# Sensor-Board.net
KiCad netlist of a schematic drawn in Altium Designer
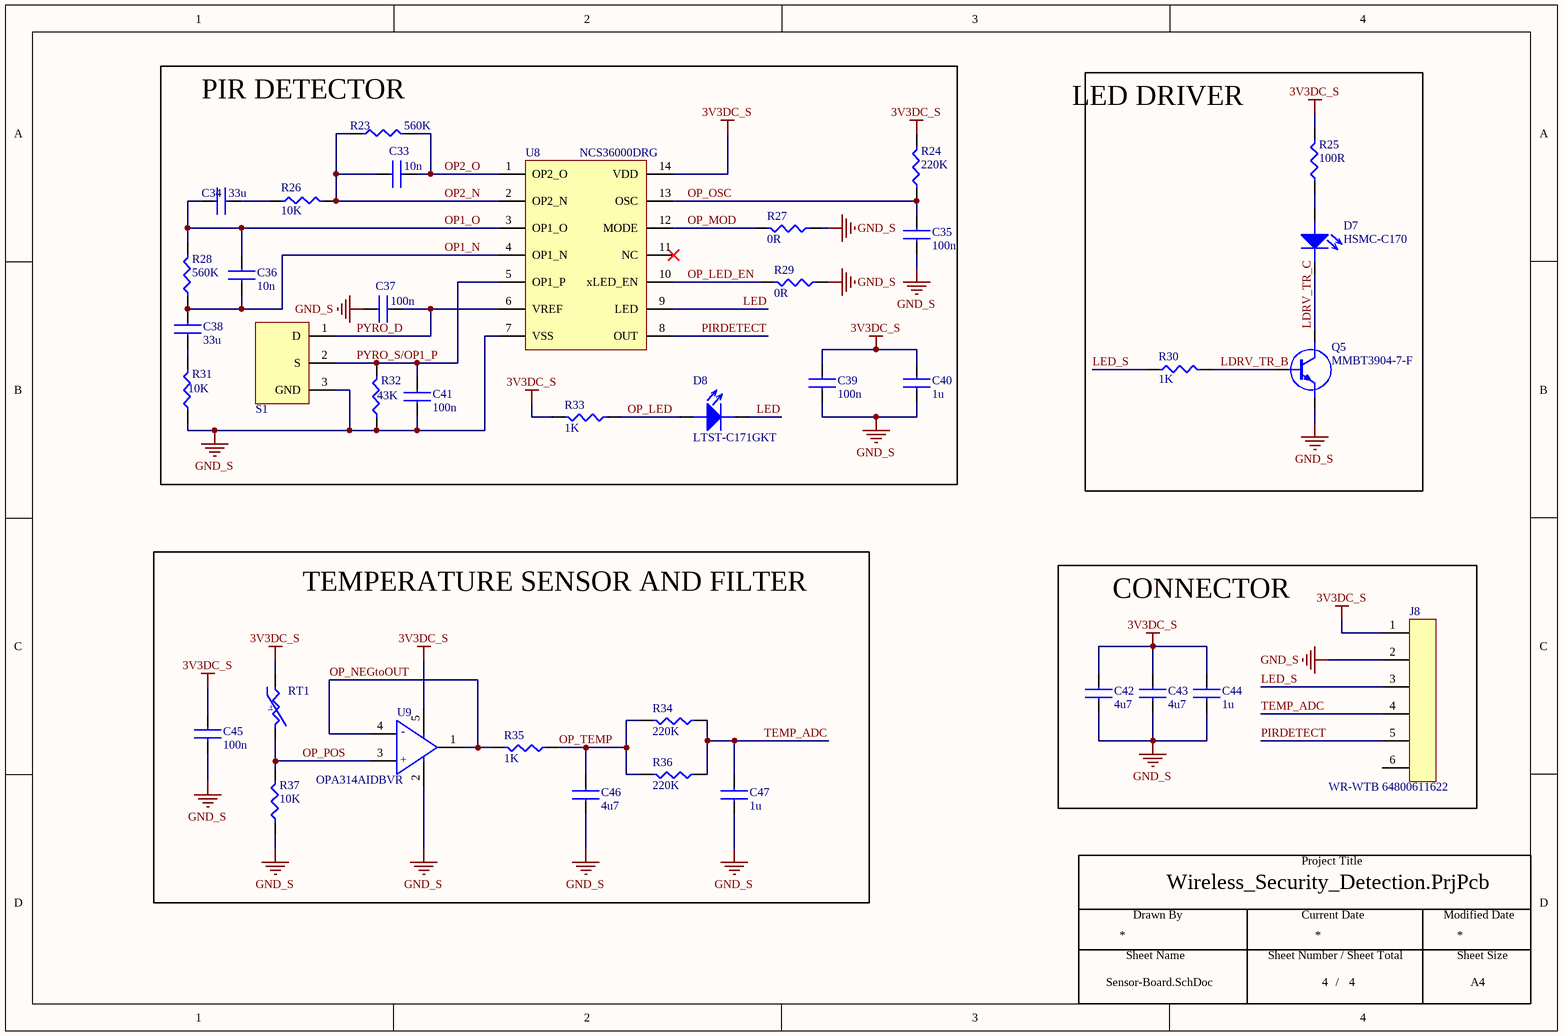
[diagram p0: Sensor-Board.SchDoc]

(export (version "E")
  (design (tool "Eeschema 10.0.6"))
  (components
    (comp (ref "C33")
      (value "10n")
      (footprint "CAPACITOR 0603")
      (description "0603 16V X7R 10nF 10% multilayer ceramic capacitor")
      (fields
        (field (name "MANUFACTURER") "Walsin Technologies")
        (field (name "MANUFACTURER PART NUMBER") "0603B103K160CT")
        (field (name "DESIGNED BY") "UK")
      )
      (libsource (lib "UKLIB") (part "CAP CER 10nF 0603"))
    )
    (comp (ref "C34")
      (value "33u")
      (footprint "CAPACITOR 1206")
      (description "Multilayer Ceramic Capacitor, 33 uF, 25 V, ± 20%, X5R, 1206 [3216 Metric]")
      (fields
        (field (name "MANUFACTURER") "TDK")
        (field (name "MANUFACTURER PART NUMBER") "C3216X5R1E336M160AC")
        (field (name "DESIGNED BY") "UK")
      )
      (libsource (lib "UKLIB") (part "CAP CER 33uF 1206"))
    )
    (comp (ref "C35")
      (value "100n")
      (footprint "Capacitor 0603")
      (description "Multilayer Ceramic Capacitor, 0.1 uF, 50 V, ± 10%, X7R, 0603 [1608 Metric]")
      (fields
        (field (name "MANUFACTURER") "KEMET")
        (field (name "MANUFACTURER PART NUMBER") "C0603C104K5RACTU")
        (field (name "DESIGNED BY") "UK")
      )
      (libsource (lib "UKLIB") (part "CAP CER 100nF 0603"))
    )
    (comp (ref "C36")
      (value "10n")
      (footprint "CAPACITOR 0603")
      (description "0603 16V X7R 10nF 10% multilayer ceramic capacitor")
      (fields
        (field (name "MANUFACTURER") "Walsin Technologies")
        (field (name "MANUFACTURER PART NUMBER") "0603B103K160CT")
        (field (name "DESIGNED BY") "UK")
      )
      (libsource (lib "UKLIB") (part "CAP CER 10nF 0603"))
    )
    (comp (ref "C37")
      (value "100n")
      (footprint "Capacitor 0603")
      (description "Multilayer Ceramic Capacitor, 0.1 uF, 50 V, ± 10%, X7R, 0603 [1608 Metric]")
      (fields
        (field (name "MANUFACTURER") "KEMET")
        (field (name "MANUFACTURER PART NUMBER") "C0603C104K5RACTU")
        (field (name "DESIGNED BY") "UK")
      )
      (libsource (lib "UKLIB") (part "CAP CER 100nF 0603"))
    )
    (comp (ref "C38")
      (value "33u")
      (footprint "CAPACITOR 1206")
      (description "Multilayer Ceramic Capacitor, 33 uF, 25 V, ± 20%, X5R, 1206 [3216 Metric]")
      (fields
        (field (name "MANUFACTURER") "TDK")
        (field (name "MANUFACTURER PART NUMBER") "C3216X5R1E336M160AC")
        (field (name "DESIGNED BY") "UK")
      )
      (libsource (lib "UKLIB") (part "CAP CER 33uF 1206"))
    )
    (comp (ref "C39")
      (value "100n")
      (footprint "Capacitor 0603")
      (description "Multilayer Ceramic Capacitor, 0.1 uF, 50 V, ± 10%, X7R, 0603 [1608 Metric]")
      (fields
        (field (name "MANUFACTURER") "KEMET")
        (field (name "MANUFACTURER PART NUMBER") "C0603C104K5RACTU")
        (field (name "DESIGNED BY") "UK")
      )
      (libsource (lib "UKLIB") (part "CAP CER 100nF 0603"))
    )
    (comp (ref "C40")
      (value "1u")
      (footprint "CAPACITOR 0805 - duplicate")
      (description "Multilayer Ceramic Capacitor, 1 uF, 50 V, ± 10%, X7R, 0805 [2012 Metric]")
      (fields
        (field (name "MANUFACTURER") "Samsung")
        (field (name "MANUFACTURER PART NUMBER") "CL21B105KBFNNNE")
        (field (name "DESIGNED BY") "UK")
      )
      (libsource (lib "UKLIB") (part "CAP CER 1uF 0805"))
    )
    (comp (ref "C41")
      (value "100n")
      (footprint "Capacitor 0603")
      (description "Multilayer Ceramic Capacitor, 0.1 uF, 50 V, ± 10%, X7R, 0603 [1608 Metric]")
      (fields
        (field (name "MANUFACTURER") "KEMET")
        (field (name "MANUFACTURER PART NUMBER") "C0603C104K5RACTU")
        (field (name "DESIGNED BY") "UK")
      )
      (libsource (lib "UKLIB") (part "CAP CER 100nF 0603"))
    )
    (comp (ref "C42")
      (value "4u7")
      (footprint "CAPACITOR 0805 - duplicate")
      (description "Multilayer Ceramic Capacitor, 4.7 uF, 25 V, ± 10%, X5R, 0805 [2012 Metric]")
      (fields
        (field (name "MANUFACTURER") "Samsung")
        (field (name "MANUFACTURER PART NUMBER") "CL21A475KAQNNNE")
        (field (name "DESIGNED BY") "UK")
      )
      (libsource (lib "UKLIB") (part "CAP CER 4.7uF 0805"))
    )
    (comp (ref "C43")
      (value "4u7")
      (footprint "CAPACITOR 0805 - duplicate")
      (description "Multilayer Ceramic Capacitor, 4.7 uF, 25 V, ± 10%, X5R, 0805 [2012 Metric]")
      (fields
        (field (name "MANUFACTURER") "Samsung")
        (field (name "MANUFACTURER PART NUMBER") "CL21A475KAQNNNE")
        (field (name "DESIGNED BY") "UK")
      )
      (libsource (lib "UKLIB") (part "CAP CER 4.7uF 0805"))
    )
    (comp (ref "C44")
      (value "1u")
      (footprint "CAPACITOR 0805 - duplicate")
      (description "Multilayer Ceramic Capacitor, 1 uF, 50 V, ± 10%, X7R, 0805 [2012 Metric]")
      (fields
        (field (name "MANUFACTURER") "Samsung")
        (field (name "MANUFACTURER PART NUMBER") "CL21B105KBFNNNE")
        (field (name "DESIGNED BY") "UK")
      )
      (libsource (lib "UKLIB") (part "CAP CER 1uF 0805"))
    )
    (comp (ref "C45")
      (value "100n")
      (footprint "Capacitor 0603")
      (description "Multilayer Ceramic Capacitor, 0.1 uF, 50 V, ± 10%, X7R, 0603 [1608 Metric]")
      (fields
        (field (name "MANUFACTURER") "KEMET")
        (field (name "MANUFACTURER PART NUMBER") "C0603C104K5RACTU")
        (field (name "DESIGNED BY") "UK")
      )
      (libsource (lib "UKLIB") (part "CAP CER 100nF 0603"))
    )
    (comp (ref "C46")
      (value "4u7")
      (footprint "CAPACITOR 0805 - duplicate")
      (description "Multilayer Ceramic Capacitor, 4.7 uF, 25 V, ± 10%, X5R, 0805 [2012 Metric]")
      (fields
        (field (name "MANUFACTURER") "Samsung")
        (field (name "MANUFACTURER PART NUMBER") "CL21A475KAQNNNE")
        (field (name "DESIGNED BY") "UK")
      )
      (libsource (lib "UKLIB") (part "CAP CER 4.7uF 0805"))
    )
    (comp (ref "C47")
      (value "1u")
      (footprint "CAPACITOR 0805 - duplicate")
      (description "Multilayer Ceramic Capacitor, 1 uF, 50 V, ± 10%, X7R, 0805 [2012 Metric]")
      (fields
        (field (name "MANUFACTURER") "Samsung")
        (field (name "MANUFACTURER PART NUMBER") "CL21B105KBFNNNE")
        (field (name "DESIGNED BY") "UK")
      )
      (libsource (lib "UKLIB") (part "CAP CER 1uF 0805"))
    )
    (comp (ref "D7")
      (value "HSMC-C170")
      (footprint "LED RED 0805")
      (description "Single Color LED, Red, Untinted Diffused, 1.4mm")
      (fields (field (name "MANUFACTURER") "Broadcom Avago") (field (name "DESIGNED BY") "UK"))
      (libsource (lib "UKLIB") (part "LED RED 0805"))
    )
    (comp (ref "D8")
      (value "LTST-C171GKT")
      (footprint "LED GREEN 0805")
      (description "LED Low-Power Uni-Color Green 565nm 2.1V 2-Pin Chip LED T/R")
      (fields (field (name "MANUFACTURER") "Vishay Lite-On") (field (name "DESIGNED BY") "UK"))
      (libsource (lib "UKLIB") (part "LED GREEN 0805"))
    )
    (comp (ref "J8")
      (value "WR-WTB 64800611622")
      (footprint "6P SMD TERMINAL 1.50 MALE")
      (description "WR-WTB Wire-to-Board Connectors 1.50 mm")
      (fields
        (field (name "MANUFACTURER") "Wurth Electronics")
        (field (name "MANUFACTURER PART NUMBER") "64800611622")
        (field (name "DESIGNED BY") "UK")
      )
      (libsource (lib "UKLIB") (part "6P SMD TERMINAL 1.50 MALE"))
    )
    (comp (ref "Q5")
      (value "MMBT3904-7-F")
      (footprint "SOT-23F")
      (description "Transistor General Purpose BJT NPN 40 Volt 0.2A Automotive 3-Pin SOT-23")
      (fields (field (name "MANUFACTURER") "Diodes Zetex") (field (name "DESIGNED BY") "UK"))
      (libsource (lib "UKLIB") (part "MMBT3904-7-F"))
    )
    (comp (ref "R23")
      (value "560K")
      (footprint "Resistor 0603")
      (description "SMD Chip Resistor, 560 kOhm, ± 5%, 100 mW, 0603 [1608 Metric], Thick Film, General Purpose")
      (fields
        (field (name "MANUFACTURER") "Yageo")
        (field (name "MANUFACTURER PART NUMBER") "RC0603JR-07560KL")
        (field (name "DESIGNED BY") "UK")
      )
      (libsource (lib "UKLIB") (part "RES 560K 0603"))
    )
    (comp (ref "R24")
      (value "220K")
      (footprint "Resistor 0603")
      (description "SMD Chip Resistor, 220 kOhm, ± 5%, 100 mW, 0603 [1608 Metric], Thick Film, General Purpose")
      (fields
        (field (name "MANUFACTURER") "Yageo")
        (field (name "MANUFACTURER PART NUMBER") "RC0603JR-07220KL")
        (field (name "DESIGNED BY") "UK")
      )
      (libsource (lib "UKLIB") (part "RES 220K 0603"))
    )
    (comp (ref "R25")
      (value "100R")
      (footprint "Resistor 0603")
      (description "SMD Chip Resistor, 100 Ohm, ± 5%, 100 mW, 0603 [1608 Metric], Thick Film, General Purpose")
      (fields
        (field (name "MANUFACTURER") "Yageo")
        (field (name "MANUFACTURER PART NUMBER") "RC0603JR-07100RL")
        (field (name "DESIGNED BY") "UK")
      )
      (libsource (lib "UKLIB") (part "RES 100R 0603"))
    )
    (comp (ref "R26")
      (value "10K")
      (footprint "Resistor 0603")
      (description "SMD Chip Resistor, 10 kOhm, ± 1%, 100 mW, 0603 [1608 Metric], Thick Film, General Purpose")
      (fields
        (field (name "MANUFACTURER") "Yageo")
        (field (name "MANUFACTURER PART NUMBER") "RC0603FR-0710KL")
        (field (name "DESIGNED BY") "UK")
      )
      (libsource (lib "UKLIB") (part "RES 10K 0603"))
    )
    (comp (ref "R27")
      (value "0R")
      (footprint "Resistor 0603")
      (description "GENERAL PURPOSE CHIP RESISTOR Metal Glaze/thick Film, 0.1W, 0ohm, Surface Mount, 0603")
      (fields
        (field (name "MANUFACTURER") "Yageo")
        (field (name "MANUFACTURER PART NUMBER") "RC0603JR-070RL")
        (field (name "DESIGNED BY") "UK")
      )
      (libsource (lib "UKLIB") (part "RES 0R 0603"))
    )
    (comp (ref "R28")
      (value "560K")
      (footprint "Resistor 0603")
      (description "SMD Chip Resistor, 560 kOhm, ± 5%, 100 mW, 0603 [1608 Metric], Thick Film, General Purpose")
      (fields
        (field (name "MANUFACTURER") "Yageo")
        (field (name "MANUFACTURER PART NUMBER") "RC0603JR-07560KL")
        (field (name "DESIGNED BY") "UK")
      )
      (libsource (lib "UKLIB") (part "RES 560K 0603"))
    )
    (comp (ref "R29")
      (value "0R")
      (footprint "Resistor 0603")
      (description "GENERAL PURPOSE CHIP RESISTOR Metal Glaze/thick Film, 0.1W, 0ohm, Surface Mount, 0603")
      (fields
        (field (name "MANUFACTURER") "Yageo")
        (field (name "MANUFACTURER PART NUMBER") "RC0603JR-070RL")
        (field (name "DESIGNED BY") "UK")
      )
      (libsource (lib "UKLIB") (part "RES 0R 0603"))
    )
    (comp (ref "R30")
      (value "1K")
      (footprint "Resistor 0603")
      (description "SMD Chip Resistor, 1 kOhm, ± 1%, 100 mW, 0603 [1608 Metric], Thick Film, General Purpose")
      (fields
        (field (name "MANUFACTURER") "Yageo")
        (field (name "MANUFACTURER PART NUMBER") "RC0603FR-071KL")
        (field (name "DESIGNED BY") "UK")
      )
      (libsource (lib "UKLIB") (part "RES 1K 0603"))
    )
    (comp (ref "R31")
      (value "10K")
      (footprint "Resistor 0603")
      (description "SMD Chip Resistor, 10 kOhm, ± 1%, 100 mW, 0603 [1608 Metric], Thick Film, General Purpose")
      (fields
        (field (name "MANUFACTURER") "Yageo")
        (field (name "MANUFACTURER PART NUMBER") "RC0603FR-0710KL")
        (field (name "DESIGNED BY") "UK")
      )
      (libsource (lib "UKLIB") (part "RES 10K 0603"))
    )
    (comp (ref "R32")
      (value "43K")
      (footprint "Resistor 0603")
      (description "Res Thick Film 0603 43K Ohm 5% 0.1W(1/10W) ±100ppm/°C Pad SMD T/R")
      (fields
        (field (name "MANUFACTURER") "Yageo")
        (field (name "MANUFACTURER PART NUMBER") "RC0603JR-0743KL")
        (field (name "DESIGNED BY") "UK")
      )
      (libsource (lib "UKLIB") (part "RES 43K 0603"))
    )
    (comp (ref "R33")
      (value "1K")
      (footprint "Resistor 0603")
      (description "SMD Chip Resistor, 1 kOhm, ± 1%, 100 mW, 0603 [1608 Metric], Thick Film, General Purpose")
      (fields
        (field (name "MANUFACTURER") "Yageo")
        (field (name "MANUFACTURER PART NUMBER") "RC0603FR-071KL")
        (field (name "DESIGNED BY") "UK")
      )
      (libsource (lib "UKLIB") (part "RES 1K 0603"))
    )
    (comp (ref "R34")
      (value "220K")
      (footprint "Resistor 0603")
      (description "SMD Chip Resistor, 220 kOhm, ± 5%, 100 mW, 0603 [1608 Metric], Thick Film, General Purpose")
      (fields
        (field (name "MANUFACTURER") "Yageo")
        (field (name "MANUFACTURER PART NUMBER") "RC0603JR-07220KL")
        (field (name "DESIGNED BY") "UK")
      )
      (libsource (lib "UKLIB") (part "RES 220K 0603"))
    )
    (comp (ref "R35")
      (value "1K")
      (footprint "Resistor 0603")
      (description "SMD Chip Resistor, 1 kOhm, ± 1%, 100 mW, 0603 [1608 Metric], Thick Film, General Purpose")
      (fields
        (field (name "MANUFACTURER") "Yageo")
        (field (name "MANUFACTURER PART NUMBER") "RC0603FR-071KL")
        (field (name "DESIGNED BY") "UK")
      )
      (libsource (lib "UKLIB") (part "RES 1K 0603"))
    )
    (comp (ref "R36")
      (value "220K")
      (footprint "Resistor 0603")
      (description "SMD Chip Resistor, 220 kOhm, ± 5%, 100 mW, 0603 [1608 Metric], Thick Film, General Purpose")
      (fields
        (field (name "MANUFACTURER") "Yageo")
        (field (name "MANUFACTURER PART NUMBER") "RC0603JR-07220KL")
        (field (name "DESIGNED BY") "UK")
      )
      (libsource (lib "UKLIB") (part "RES 220K 0603"))
    )
    (comp (ref "R37")
      (value "10K")
      (footprint "Resistor 0603")
      (description "SMD Chip Resistor, 10 kOhm, ± 1%, 100 mW, 0603 [1608 Metric], Thick Film, General Purpose")
      (fields
        (field (name "MANUFACTURER") "Yageo")
        (field (name "MANUFACTURER PART NUMBER") "RC0603FR-0710KL")
        (field (name "DESIGNED BY") "UK")
      )
      (libsource (lib "UKLIB") (part "RES 10K 0603"))
    )
    (comp (ref "RT1")
      (value "TFPT1206L1002FM")
      (footprint "RESISTOR 1206")
      (description "Thermistor PTC 10K Ohm 1% 2-Pin 1206 Surface Mount Solder Pad T/R Automotive")
      (fields
        (field (name "MANUFACTURER") "Vishay Dale")
        (field (name "TOLERANCE") "1%")
        (field (name "DESIGNED BY") "UK")
      )
      (libsource (lib "UKLIB") (part "TFPT1206L1002FM"))
    )
    (comp (ref "S1")
      (value "LHI 878/3902")
      (footprint "LHI 878")
      (description "Sensor Pyro Detector Dual Motion")
      (fields
        (field (name "MANUFACTURER") "Excelitas")
        (field (name "MANUFACTURER PART NUMBER") "LHI878/3902")
        (field (name "DESIGNED BY") "UK")
      )
      (libsource (lib "UKLIB") (part "LHI 878/3902"))
    )
    (comp (ref "U8")
      (value "NCS36000DRG")
      (footprint "SOIC-14")
      (description "NCS36000 Series Single 5.75V Passive Infrared Detector Controller (PIR) -SOIC-14")
      (fields (field (name "MANUFACTURER") "ON Semiconductor") (field (name "DESIGNED BY") "UK"))
      (libsource (lib "UKLIB") (part "NCS36000DRG"))
    )
    (comp (ref "U9")
      (value "OPA314AIDBVR")
      (footprint "SOT23-5")
      (description "IC OPAMP GP 3MHZ RRO SOT23-5")
      (fields (field (name "MANUFACTURER") "Texas Instruments") (field (name "DESIGNED BY") "UK"))
      (libsource (lib "UKLIB") (part "OPA314AIDBVR"))
    )
  )
  (nets
    (net (code "1") (name "/LDRV_TR_B") (class "Default")
      (node (ref "Q5") (pin "1") (pinfunction "B_1") (pintype "passive"))
      (node (ref "R30") (pin "2") (pinfunction "2_2") (pintype "passive"))
    )
    (net (code "2") (name "/LDRV_TR_C") (class "Default")
      (node (ref "D7") (pin "2") (pinfunction "C_2") (pintype "passive"))
      (node (ref "Q5") (pin "3") (pinfunction "C_3") (pintype "passive"))
    )
    (net (code "3") (name "/LED") (class "Default")
      (node (ref "D8") (pin "2") (pinfunction "C_2") (pintype "passive"))
      (node (ref "U8") (pin "9") (pinfunction "LED_9") (pintype "passive"))
    )
    (net (code "4") (name "/LED_S") (class "Default")
      (node (ref "J8") (pin "3") (pinfunction "3_3") (pintype "passive"))
      (node (ref "R30") (pin "1") (pinfunction "1_1") (pintype "passive"))
    )
    (net (code "5") (name "/OP1_N") (class "Default")
      (node (ref "C36") (pin "1") (pinfunction "1_1") (pintype "passive"))
      (node (ref "C38") (pin "2") (pinfunction "2_2") (pintype "passive"))
      (node (ref "R28") (pin "1") (pinfunction "1_1") (pintype "passive"))
      (node (ref "U8") (pin "4") (pinfunction "OP1_N_4") (pintype "passive"))
    )
    (net (code "6") (name "/OP1_O") (class "Default")
      (node (ref "C34") (pin "1") (pinfunction "1_1") (pintype "passive"))
      (node (ref "C36") (pin "2") (pinfunction "2_2") (pintype "passive"))
      (node (ref "R28") (pin "2") (pinfunction "2_2") (pintype "passive"))
      (node (ref "U8") (pin "3") (pinfunction "OP1_O_3") (pintype "passive"))
    )
    (net (code "7") (name "/OP2_N") (class "Default")
      (node (ref "C33") (pin "1") (pinfunction "1_1") (pintype "passive"))
      (node (ref "R23") (pin "1") (pinfunction "1_1") (pintype "passive"))
      (node (ref "R26") (pin "2") (pinfunction "2_2") (pintype "passive"))
      (node (ref "U8") (pin "2") (pinfunction "OP2_N_2") (pintype "passive"))
    )
    (net (code "8") (name "/OP2_O") (class "Default")
      (node (ref "C33") (pin "2") (pinfunction "2_2") (pintype "passive"))
      (node (ref "R23") (pin "2") (pinfunction "2_2") (pintype "passive"))
      (node (ref "U8") (pin "1") (pinfunction "OP2_O_1") (pintype "passive"))
    )
    (net (code "9") (name "/OP_LED") (class "Default")
      (node (ref "D8") (pin "1") (pinfunction "A_1") (pintype "passive"))
      (node (ref "R33") (pin "1") (pinfunction "1_1") (pintype "passive"))
    )
    (net (code "10") (name "/OP_LED_EN") (class "Default")
      (node (ref "R29") (pin "2") (pinfunction "2_2") (pintype "passive"))
      (node (ref "U8") (pin "10") (pinfunction "xLED_EN_10") (pintype "passive"))
    )
    (net (code "11") (name "/OP_MOD") (class "Default")
      (node (ref "R27") (pin "2") (pinfunction "2_2") (pintype "passive"))
      (node (ref "U8") (pin "12") (pinfunction "MODE_12") (pintype "passive"))
    )
    (net (code "12") (name "/OP_NEGtoOUT") (class "Default")
      (node (ref "R35") (pin "2") (pinfunction "2_2") (pintype "passive"))
      (node (ref "U9") (pin "1") (pinfunction "OUT_1") (pintype "passive"))
      (node (ref "U9") (pin "4") (pinfunction "-IN_4") (pintype "passive"))
    )
    (net (code "13") (name "/OP_OSC") (class "Default")
      (node (ref "C35") (pin "2") (pinfunction "2_2") (pintype "passive"))
      (node (ref "R24") (pin "1") (pinfunction "1_1") (pintype "passive"))
      (node (ref "U8") (pin "13") (pinfunction "OSC_13") (pintype "passive"))
    )
    (net (code "14") (name "/OP_POS") (class "Default")
      (node (ref "R37") (pin "2") (pinfunction "2_2") (pintype "passive"))
      (node (ref "RT1") (pin "2") (pinfunction "2_2") (pintype "passive"))
      (node (ref "U9") (pin "3") (pinfunction "+IN_3") (pintype "passive"))
    )
    (net (code "15") (name "/OP_TEMP") (class "Default")
      (node (ref "C46") (pin "1") (pinfunction "1_1") (pintype "passive"))
      (node (ref "R34") (pin "2") (pinfunction "2_2") (pintype "passive"))
      (node (ref "R35") (pin "1") (pinfunction "1_1") (pintype "passive"))
      (node (ref "R36") (pin "2") (pinfunction "2_2") (pintype "passive"))
    )
    (net (code "16") (name "/PIRDETECT") (class "Default")
      (node (ref "J8") (pin "5") (pinfunction "5_5") (pintype "passive"))
      (node (ref "U8") (pin "8") (pinfunction "OUT_8") (pintype "passive"))
    )
    (net (code "17") (name "/PYRO_D") (class "Default")
      (node (ref "C37") (pin "1") (pinfunction "1_1") (pintype "passive"))
      (node (ref "S1") (pin "1") (pinfunction "D_1") (pintype "passive"))
      (node (ref "U8") (pin "6") (pinfunction "VREF_6") (pintype "passive"))
    )
    (net (code "18") (name "/PYRO_S{slash}OP1_P") (class "Default")
      (node (ref "C41") (pin "2") (pinfunction "2_2") (pintype "passive"))
      (node (ref "R32") (pin "2") (pinfunction "2_2") (pintype "passive"))
      (node (ref "S1") (pin "2") (pinfunction "S_2") (pintype "passive"))
      (node (ref "U8") (pin "5") (pinfunction "OP1_P_5") (pintype "passive"))
    )
    (net (code "19") (name "/TEMP_ADC") (class "Default")
      (node (ref "C47") (pin "2") (pinfunction "2_2") (pintype "passive"))
      (node (ref "J8") (pin "4") (pinfunction "4_4") (pintype "passive"))
      (node (ref "R34") (pin "1") (pinfunction "1_1") (pintype "passive"))
      (node (ref "R36") (pin "1") (pinfunction "1_1") (pintype "passive"))
    )
    (net (code "20") (name "3V3DC_S") (class "Default")
      (node (ref "C39") (pin "2") (pinfunction "2_2") (pintype "passive"))
      (node (ref "C40") (pin "2") (pinfunction "2_2") (pintype "passive"))
      (node (ref "C42") (pin "2") (pinfunction "2_2") (pintype "passive"))
      (node (ref "C43") (pin "2") (pinfunction "2_2") (pintype "passive"))
      (node (ref "C44") (pin "2") (pinfunction "2_2") (pintype "passive"))
      (node (ref "C45") (pin "2") (pinfunction "2_2") (pintype "passive"))
      (node (ref "J8") (pin "1") (pinfunction "1_1") (pintype "passive"))
      (node (ref "R24") (pin "2") (pinfunction "2_2") (pintype "passive"))
      (node (ref "R25") (pin "2") (pinfunction "2_2") (pintype "passive"))
      (node (ref "R33") (pin "2") (pinfunction "2_2") (pintype "passive"))
      (node (ref "RT1") (pin "1") (pinfunction "1_1") (pintype "passive"))
      (node (ref "U8") (pin "14") (pinfunction "VDD_14") (pintype "passive"))
      (node (ref "U9") (pin "5") (pinfunction "V+_5") (pintype "passive"))
    )
    (net (code "21") (name "GND_S") (class "Default")
      (node (ref "C35") (pin "1") (pinfunction "1_1") (pintype "passive"))
      (node (ref "C37") (pin "2") (pinfunction "2_2") (pintype "passive"))
      (node (ref "C39") (pin "1") (pinfunction "1_1") (pintype "passive"))
      (node (ref "C40") (pin "1") (pinfunction "1_1") (pintype "passive"))
      (node (ref "C41") (pin "1") (pinfunction "1_1") (pintype "passive"))
      (node (ref "C42") (pin "1") (pinfunction "1_1") (pintype "passive"))
      (node (ref "C43") (pin "1") (pinfunction "1_1") (pintype "passive"))
      (node (ref "C44") (pin "1") (pinfunction "1_1") (pintype "passive"))
      (node (ref "C45") (pin "1") (pinfunction "1_1") (pintype "passive"))
      (node (ref "C46") (pin "2") (pinfunction "2_2") (pintype "passive"))
      (node (ref "C47") (pin "1") (pinfunction "1_1") (pintype "passive"))
      (node (ref "J8") (pin "2") (pinfunction "2_2") (pintype "passive"))
      (node (ref "Q5") (pin "2") (pinfunction "E_2") (pintype "passive"))
      (node (ref "R27") (pin "1") (pinfunction "1_1") (pintype "passive"))
      (node (ref "R29") (pin "1") (pinfunction "1_1") (pintype "passive"))
      (node (ref "R31") (pin "1") (pinfunction "1_1") (pintype "passive"))
      (node (ref "R32") (pin "1") (pinfunction "1_1") (pintype "passive"))
      (node (ref "R37") (pin "1") (pinfunction "1_1") (pintype "passive"))
      (node (ref "S1") (pin "3") (pinfunction "GND_3") (pintype "passive"))
      (node (ref "U8") (pin "7") (pinfunction "VSS_7") (pintype "passive"))
      (node (ref "U9") (pin "2") (pinfunction "V–_2") (pintype "passive"))
    )
    (net (code "22") (name "Net-(C34-Pad2)") (class "Default")
      (node (ref "C34") (pin "2") (pinfunction "2_2") (pintype "passive"))
      (node (ref "R26") (pin "1") (pinfunction "1_1") (pintype "passive"))
    )
    (net (code "23") (name "Net-(C38-Pad1)") (class "Default")
      (node (ref "C38") (pin "1") (pinfunction "1_1") (pintype "passive"))
      (node (ref "R31") (pin "2") (pinfunction "2_2") (pintype "passive"))
    )
    (net (code "24") (name "Net-(D7-A)") (class "Default")
      (node (ref "D7") (pin "1") (pinfunction "A_1") (pintype "passive"))
      (node (ref "R25") (pin "1") (pinfunction "1_1") (pintype "passive"))
    )
    (net (code "25") (name "unconnected-(J8-Pad6)") (class "Default")
      (node (ref "J8") (pin "6") (pinfunction "6_6") (pintype "passive"))
    )
    (net (code "26") (name "unconnected-(U8-NC-Pad11)") (class "Default")
      (node (ref "U8") (pin "11") (pinfunction "NC_11") (pintype "passive+no_connect"))
    )
  )
)
